# v3.net
KiCad netlist of a schematic drawn in EAGLE
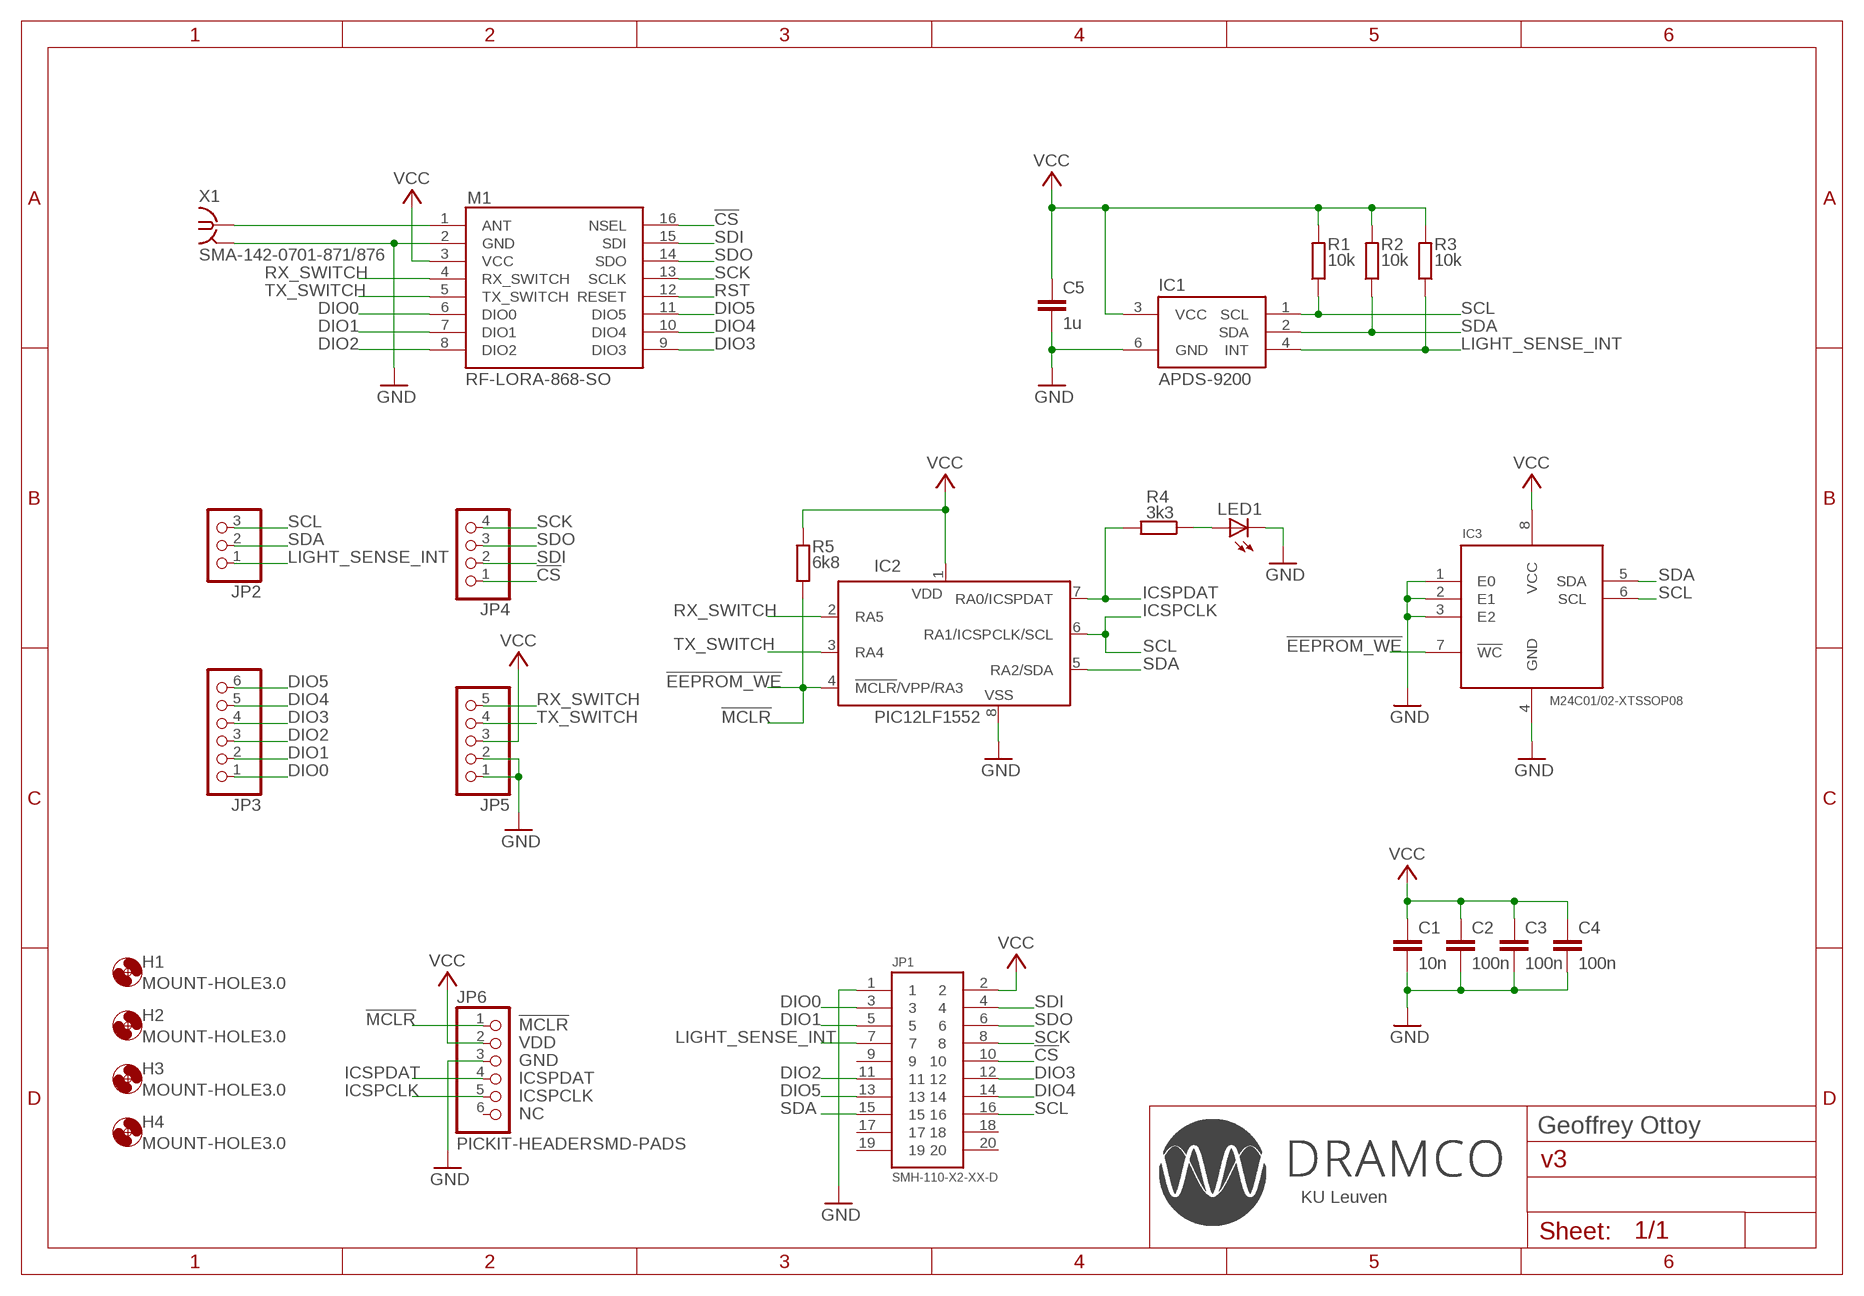
[diagram p0: schematic, sheet 1]

(export (version "E")
  (design (tool "Eeschema 10.0.6"))
  (components
    (comp (ref "C1")
      (value "10n")
      (footprint "eagle-import:C0805K")
      (libsource (lib "eagle-import") (part "C-EUC0805K"))
    )
    (comp (ref "C2")
      (value "100n")
      (footprint "eagle-import:C0805K")
      (libsource (lib "eagle-import") (part "C-EUC0805K"))
    )
    (comp (ref "C3")
      (value "100n")
      (footprint "eagle-import:C0805K")
      (libsource (lib "eagle-import") (part "C-EUC0805K"))
    )
    (comp (ref "C4")
      (value "100n")
      (footprint "eagle-import:C0805K")
      (libsource (lib "eagle-import") (part "C-EUC0805K"))
    )
    (comp (ref "C5")
      (value "1u")
      (footprint "eagle-import:C0805K")
      (libsource (lib "eagle-import") (part "C-EUC0805K"))
    )
    (comp (ref "H1")
      (value "MOUNT-HOLE3.0")
      (footprint "eagle-import:3,0")
      (libsource (lib "eagle-import") (part "MOUNT-HOLE3.0"))
    )
    (comp (ref "H2")
      (value "MOUNT-HOLE3.0")
      (footprint "eagle-import:3,0")
      (libsource (lib "eagle-import") (part "MOUNT-HOLE3.0"))
    )
    (comp (ref "H3")
      (value "MOUNT-HOLE3.0")
      (footprint "eagle-import:3,0")
      (libsource (lib "eagle-import") (part "MOUNT-HOLE3.0"))
    )
    (comp (ref "H4")
      (value "MOUNT-HOLE3.0")
      (footprint "eagle-import:3,0")
      (libsource (lib "eagle-import") (part "MOUNT-HOLE3.0"))
    )
    (comp (ref "IC1")
      (value "APDS-9200")
      (footprint "eagle-import:APDS-9200")
      (libsource (lib "eagle-import") (part "APDS-9200"))
    )
    (comp (ref "IC2")
      (value "PIC12LF1552")
      (footprint "eagle-import:MSOP8")
      (libsource (lib "eagle-import") (part "PIC12LF1552"))
    )
    (comp (ref "IC3")
      (value "M24C01/02-XTSSOP08")
      (footprint "eagle-import:TSSOP08")
      (libsource (lib "eagle-import") (part "M24C01/02-XTSSOP08"))
    )
    (comp (ref "JP1")
      (value "SMH-110-X2-XX-D")
      (footprint "eagle-import:SMH-110-X2-XX-D")
      (libsource (lib "eagle-import") (part "SMH-110-X2-XX-D"))
    )
    (comp (ref "JP2")
      (value "PINHD-1X3")
      (footprint "eagle-import:1X03")
      (libsource (lib "eagle-import") (part "PINHD-1X3"))
    )
    (comp (ref "JP3")
      (value "PINHD-1X6")
      (footprint "eagle-import:1X06")
      (libsource (lib "eagle-import") (part "PINHD-1X6"))
    )
    (comp (ref "JP4")
      (value "PINHD-1X4")
      (footprint "eagle-import:1X04")
      (libsource (lib "eagle-import") (part "PINHD-1X4"))
    )
    (comp (ref "JP5")
      (value "PINHD-1X5")
      (footprint "eagle-import:1X05")
      (libsource (lib "eagle-import") (part "PINHD-1X5"))
    )
    (comp (ref "JP6")
      (value "PICKIT-HEADERSMD-PADS")
      (footprint "eagle-import:1X06_SMD")
      (libsource (lib "eagle-import") (part "PICKIT-HEADERSMD-PADS"))
    )
    (comp (ref "LED1")
      (value "LEDCHIP-LED0805")
      (footprint "eagle-import:CHIP-LED0805")
      (libsource (lib "eagle-import") (part "LEDCHIP-LED0805"))
    )
    (comp (ref "M1")
      (value "RF-LORA-868-SO")
      (footprint "eagle-import:RF-LORA-868-SO")
      (libsource (lib "eagle-import") (part "RF-LORA-868-SO"))
    )
    (comp (ref "R1")
      (value "10k")
      (footprint "eagle-import:M0805")
      (libsource (lib "eagle-import") (part "R-EU_M0805"))
    )
    (comp (ref "R2")
      (value "10k")
      (footprint "eagle-import:M0805")
      (libsource (lib "eagle-import") (part "R-EU_M0805"))
    )
    (comp (ref "R3")
      (value "10k")
      (footprint "eagle-import:M0805")
      (libsource (lib "eagle-import") (part "R-EU_M0805"))
    )
    (comp (ref "R4")
      (value "3k3")
      (footprint "eagle-import:M0805")
      (libsource (lib "eagle-import") (part "R-EU_M0805"))
    )
    (comp (ref "R5")
      (value "6k8")
      (footprint "eagle-import:M0805")
      (libsource (lib "eagle-import") (part "R-EU_M0805"))
    )
    (comp (ref "X1")
      (value "SMA-142-0701-871/876")
      (footprint "eagle-import:J502-ND-142-0701-871_876")
      (fields (field (name "MF") "JOHNSON COMPONENTS") (field (name "MPN") "142-0701-871"))
      (libsource (lib "eagle-import") (part "SMA-142-0701-871/876"))
    )
  )
  (nets
    (net (code "1") (name "/DIO0") (class "Default")
      (node (ref "JP1") (pin "3") (pinfunction "3_3") (pintype "bidirectional"))
      (node (ref "JP3") (pin "1") (pinfunction "1_1") (pintype "passive"))
      (node (ref "M1") (pin "6") (pinfunction "DIO0_6") (pintype "bidirectional"))
    )
    (net (code "2") (name "/DIO1") (class "Default")
      (node (ref "JP1") (pin "5") (pinfunction "5_5") (pintype "bidirectional"))
      (node (ref "JP3") (pin "2") (pinfunction "2_2") (pintype "passive"))
      (node (ref "M1") (pin "7") (pinfunction "DIO1_7") (pintype "bidirectional"))
    )
    (net (code "3") (name "/DIO2") (class "Default")
      (node (ref "JP1") (pin "11") (pinfunction "11_11") (pintype "bidirectional"))
      (node (ref "JP3") (pin "3") (pinfunction "3_3") (pintype "passive"))
      (node (ref "M1") (pin "8") (pinfunction "DIO2_8") (pintype "bidirectional"))
    )
    (net (code "4") (name "/DIO3") (class "Default")
      (node (ref "JP1") (pin "12") (pinfunction "12_12") (pintype "bidirectional"))
      (node (ref "JP3") (pin "4") (pinfunction "4_4") (pintype "passive"))
      (node (ref "M1") (pin "9") (pinfunction "DIO3_9") (pintype "bidirectional"))
    )
    (net (code "5") (name "/DIO4") (class "Default")
      (node (ref "JP1") (pin "14") (pinfunction "14_14") (pintype "bidirectional"))
      (node (ref "JP3") (pin "5") (pinfunction "5_5") (pintype "passive"))
      (node (ref "M1") (pin "10") (pinfunction "DIO4_10") (pintype "bidirectional"))
    )
    (net (code "6") (name "/DIO5") (class "Default")
      (node (ref "JP1") (pin "13") (pinfunction "13_13") (pintype "bidirectional"))
      (node (ref "JP3") (pin "6") (pinfunction "6_6") (pintype "passive"))
      (node (ref "M1") (pin "11") (pinfunction "DIO5_11") (pintype "bidirectional"))
    )
    (net (code "7") (name "/ICSPDAT") (class "Default")
      (node (ref "IC2") (pin "7") (pinfunction "RA0/ICSPDAT_7") (pintype "bidirectional"))
      (node (ref "JP6") (pin "4") (pinfunction "4_4") (pintype "passive"))
      (node (ref "R4") (pin "2") (pinfunction "2_2") (pintype "passive"))
    )
    (net (code "8") (name "/LIGHT_SENSE_INT") (class "Default")
      (node (ref "IC1") (pin "4") (pinfunction "INT_4") (pintype "bidirectional"))
      (node (ref "JP1") (pin "7") (pinfunction "7_7") (pintype "bidirectional"))
      (node (ref "JP2") (pin "1") (pinfunction "1_1") (pintype "passive"))
      (node (ref "R3") (pin "1") (pinfunction "1_1") (pintype "passive"))
    )
    (net (code "9") (name "/RST") (class "Default")
      (node (ref "M1") (pin "12") (pinfunction "RESET_12") (pintype "bidirectional"))
    )
    (net (code "10") (name "/RX_SWITCH") (class "Default")
      (node (ref "IC2") (pin "2") (pinfunction "RA5_2") (pintype "bidirectional"))
      (node (ref "JP5") (pin "5") (pinfunction "5_5") (pintype "passive"))
      (node (ref "M1") (pin "4") (pinfunction "RX_SWITCH_4") (pintype "bidirectional"))
    )
    (net (code "11") (name "/SCK") (class "Default")
      (node (ref "JP1") (pin "8") (pinfunction "8_8") (pintype "bidirectional"))
      (node (ref "JP4") (pin "4") (pinfunction "4_4") (pintype "passive"))
      (node (ref "M1") (pin "13") (pinfunction "SCLK_13") (pintype "bidirectional"))
    )
    (net (code "12") (name "/SCL") (class "Default")
      (node (ref "IC1") (pin "1") (pinfunction "SCL_1") (pintype "bidirectional"))
      (node (ref "IC2") (pin "6") (pinfunction "RA1/ICSPCLK/SCL_6") (pintype "bidirectional"))
      (node (ref "IC3") (pin "6") (pinfunction "SCL_6") (pintype "bidirectional"))
      (node (ref "JP1") (pin "16") (pinfunction "16_16") (pintype "bidirectional"))
      (node (ref "JP2") (pin "3") (pinfunction "3_3") (pintype "passive"))
      (node (ref "JP6") (pin "5") (pinfunction "5_5") (pintype "passive"))
      (node (ref "R1") (pin "1") (pinfunction "1_1") (pintype "passive"))
    )
    (net (code "13") (name "/SDA") (class "Default")
      (node (ref "IC1") (pin "2") (pinfunction "SDA_2") (pintype "bidirectional"))
      (node (ref "IC2") (pin "5") (pinfunction "RA2/SDA_5") (pintype "bidirectional"))
      (node (ref "IC3") (pin "5") (pinfunction "SDA_5") (pintype "bidirectional"))
      (node (ref "JP1") (pin "15") (pinfunction "15_15") (pintype "bidirectional"))
      (node (ref "JP2") (pin "2") (pinfunction "2_2") (pintype "passive"))
      (node (ref "R2") (pin "1") (pinfunction "1_1") (pintype "passive"))
    )
    (net (code "14") (name "/SDI") (class "Default")
      (node (ref "JP1") (pin "4") (pinfunction "4_4") (pintype "bidirectional"))
      (node (ref "JP4") (pin "2") (pinfunction "2_2") (pintype "passive"))
      (node (ref "M1") (pin "15") (pinfunction "SDI_15") (pintype "bidirectional"))
    )
    (net (code "15") (name "/SDO") (class "Default")
      (node (ref "JP1") (pin "6") (pinfunction "6_6") (pintype "bidirectional"))
      (node (ref "JP4") (pin "3") (pinfunction "3_3") (pintype "passive"))
      (node (ref "M1") (pin "14") (pinfunction "SDO_14") (pintype "bidirectional"))
    )
    (net (code "16") (name "/TX_SWITCH") (class "Default")
      (node (ref "IC2") (pin "3") (pinfunction "RA4_3") (pintype "bidirectional"))
      (node (ref "JP5") (pin "4") (pinfunction "4_4") (pintype "passive"))
      (node (ref "M1") (pin "5") (pinfunction "TX_SWITCH_5") (pintype "bidirectional"))
    )
    (net (code "17") (name "/~{CS}") (class "Default")
      (node (ref "JP1") (pin "10") (pinfunction "10_10") (pintype "bidirectional"))
      (node (ref "JP4") (pin "1") (pinfunction "1_1") (pintype "passive"))
      (node (ref "M1") (pin "16") (pinfunction "NSEL_16") (pintype "bidirectional"))
    )
    (net (code "18") (name "/~{MCLR}") (class "Default")
      (node (ref "IC2") (pin "4") (pinfunction "~{MCLR}/VPP/RA3_4") (pintype "input"))
      (node (ref "IC3") (pin "7") (pinfunction "~{WC}_7") (pintype "bidirectional"))
      (node (ref "JP6") (pin "1") (pinfunction "1_1") (pintype "passive"))
      (node (ref "R5") (pin "1") (pinfunction "1_1") (pintype "passive"))
    )
    (net (code "19") (name "GND") (class "Default")
      (node (ref "C1") (pin "2") (pinfunction "2_2") (pintype "passive"))
      (node (ref "C2") (pin "2") (pinfunction "2_2") (pintype "passive"))
      (node (ref "C3") (pin "2") (pinfunction "2_2") (pintype "passive"))
      (node (ref "C4") (pin "2") (pinfunction "2_2") (pintype "passive"))
      (node (ref "C5") (pin "2") (pinfunction "2_2") (pintype "passive"))
      (node (ref "IC1") (pin "6") (pinfunction "GND_6") (pintype "bidirectional"))
      (node (ref "IC2") (pin "8") (pinfunction "VSS_8") (pintype "power_in"))
      (node (ref "IC3") (pin "1") (pinfunction "E0_1") (pintype "bidirectional"))
      (node (ref "IC3") (pin "2") (pinfunction "E1_2") (pintype "bidirectional"))
      (node (ref "IC3") (pin "3") (pinfunction "E2_3") (pintype "bidirectional"))
      (node (ref "IC3") (pin "4") (pinfunction "GND_4") (pintype "bidirectional"))
      (node (ref "JP1") (pin "1") (pinfunction "1_1") (pintype "bidirectional"))
      (node (ref "JP5") (pin "1") (pinfunction "1_1") (pintype "passive"))
      (node (ref "JP5") (pin "2") (pinfunction "2_2") (pintype "passive"))
      (node (ref "JP6") (pin "3") (pinfunction "3_3") (pintype "passive"))
      (node (ref "LED1") (pin "C") (pinfunction "C_C") (pintype "passive"))
      (node (ref "M1") (pin "2") (pinfunction "GND_2") (pintype "bidirectional"))
      (node (ref "X1") (pin "G@1") (pinfunction "2_G@1") (pintype "passive"))
      (node (ref "X1") (pin "G@2") (pinfunction "2_G@2") (pintype "passive"))
      (node (ref "X1") (pin "G@3") (pinfunction "2_G@3") (pintype "passive"))
      (node (ref "X1") (pin "G@4") (pinfunction "2_G@4") (pintype "passive"))
    )
    (net (code "20") (name "Net-(LED1-PadA)") (class "Default")
      (node (ref "LED1") (pin "A") (pinfunction "A_A") (pintype "passive"))
      (node (ref "R4") (pin "1") (pinfunction "1_1") (pintype "passive"))
    )
    (net (code "21") (name "Net-(M1-ANT)") (class "Default")
      (node (ref "M1") (pin "1") (pinfunction "ANT_1") (pintype "bidirectional"))
      (node (ref "X1") (pin "1") (pinfunction "1_1") (pintype "passive"))
    )
    (net (code "22") (name "VCC") (class "Default")
      (node (ref "C1") (pin "1") (pinfunction "1_1") (pintype "passive"))
      (node (ref "C2") (pin "1") (pinfunction "1_1") (pintype "passive"))
      (node (ref "C3") (pin "1") (pinfunction "1_1") (pintype "passive"))
      (node (ref "C4") (pin "1") (pinfunction "1_1") (pintype "passive"))
      (node (ref "C5") (pin "1") (pinfunction "1_1") (pintype "passive"))
      (node (ref "IC1") (pin "3") (pinfunction "VCC_3") (pintype "bidirectional"))
      (node (ref "IC2") (pin "1") (pinfunction "VDD_1") (pintype "power_in"))
      (node (ref "IC3") (pin "8") (pinfunction "VCC_8") (pintype "bidirectional"))
      (node (ref "JP1") (pin "2") (pinfunction "2_2") (pintype "bidirectional"))
      (node (ref "JP5") (pin "3") (pinfunction "3_3") (pintype "passive"))
      (node (ref "JP6") (pin "2") (pinfunction "2_2") (pintype "passive"))
      (node (ref "M1") (pin "3") (pinfunction "VCC_3") (pintype "bidirectional"))
      (node (ref "R1") (pin "2") (pinfunction "2_2") (pintype "passive"))
      (node (ref "R2") (pin "2") (pinfunction "2_2") (pintype "passive"))
      (node (ref "R3") (pin "2") (pinfunction "2_2") (pintype "passive"))
      (node (ref "R5") (pin "2") (pinfunction "2_2") (pintype "passive"))
    )
    (net (code "23") (name "unconnected-(JP1-Pad9)") (class "Default")
      (node (ref "JP1") (pin "9") (pinfunction "9_9") (pintype "bidirectional"))
    )
    (net (code "24") (name "unconnected-(JP1-Pad17)") (class "Default")
      (node (ref "JP1") (pin "17") (pinfunction "17_17") (pintype "bidirectional"))
    )
    (net (code "25") (name "unconnected-(JP1-Pad18)") (class "Default")
      (node (ref "JP1") (pin "18") (pinfunction "18_18") (pintype "bidirectional"))
    )
    (net (code "26") (name "unconnected-(JP1-Pad19)") (class "Default")
      (node (ref "JP1") (pin "19") (pinfunction "19_19") (pintype "bidirectional"))
    )
    (net (code "27") (name "unconnected-(JP1-Pad20)") (class "Default")
      (node (ref "JP1") (pin "20") (pinfunction "20_20") (pintype "bidirectional"))
    )
    (net (code "28") (name "unconnected-(JP6-Pad6)") (class "Default")
      (node (ref "JP6") (pin "6") (pinfunction "6_6") (pintype "passive"))
    )
  )
)
